# Adafruit_PiMiniTFT_240x240.net
KiCad netlist of a schematic drawn in EAGLE
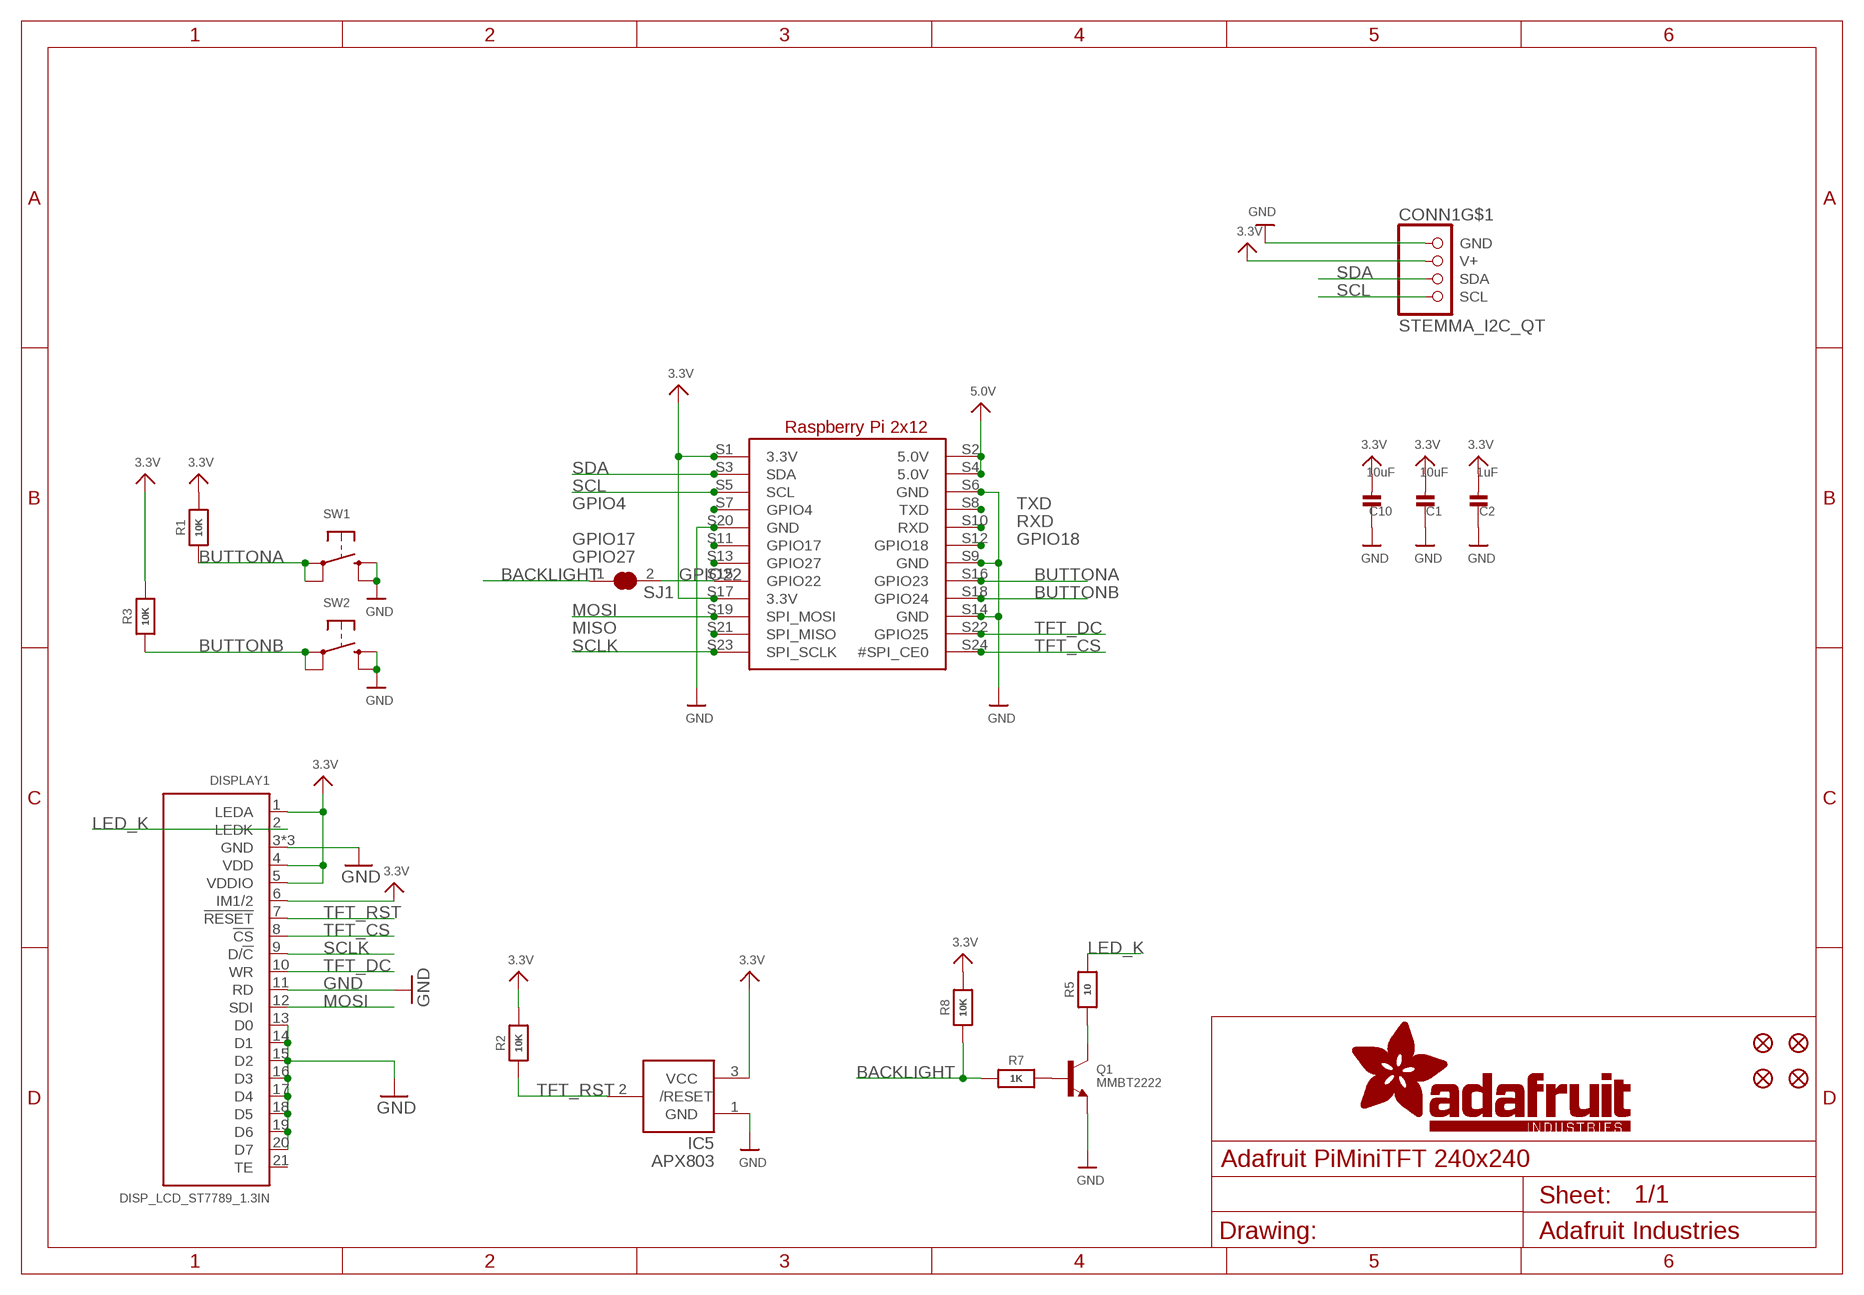
[diagram p0: schematic, sheet 1]

(export (version "E")
  (design (tool "Eeschema 10.0.6"))
  (components
    (comp (ref "C1")
      (value "10uF")
      (footprint "eagle-import:0805-NO")
      (libsource (lib "eagle-import") (part "CAP_CERAMIC0805-NOOUTLINE"))
    )
    (comp (ref "C2")
      (value "1uF")
      (footprint "eagle-import:0603-NO")
      (libsource (lib "eagle-import") (part "CAP_CERAMIC0603_NO"))
    )
    (comp (ref "C10")
      (value "10uF")
      (footprint "eagle-import:0805-NO")
      (libsource (lib "eagle-import") (part "CAP_CERAMIC0805-NOOUTLINE"))
    )
    (comp (ref "CONN1")
      (value "STEMMA_I2C_QT")
      (footprint "eagle-import:JST_SH4")
      (libsource (lib "eagle-import") (part "STEMMA_I2C_QT"))
    )
    (comp (ref "DISPLAY1")
      (value "DISP_LCD_ST7789_1.3IN")
      (footprint "eagle-import:TFT_1.3IN_240X240_24P")
      (libsource (lib "eagle-import") (part "DISP_LCD_ST7789_1.3IN"))
    )
    (comp (ref "FID1")
      (value "FIDUCIAL_1MM")
      (footprint "eagle-import:FIDUCIAL_1MM")
      (libsource (lib "eagle-import") (part "FIDUCIAL_1MM"))
    )
    (comp (ref "FID2")
      (value "FIDUCIAL_1MM")
      (footprint "eagle-import:FIDUCIAL_1MM")
      (libsource (lib "eagle-import") (part "FIDUCIAL_1MM"))
    )
    (comp (ref "FID3")
      (value "FIDUCIAL_1MM")
      (footprint "eagle-import:FIDUCIAL_1MM")
      (libsource (lib "eagle-import") (part "FIDUCIAL_1MM"))
    )
    (comp (ref "FID4")
      (value "FIDUCIAL_1MM")
      (footprint "eagle-import:FIDUCIAL_1MM")
      (libsource (lib "eagle-import") (part "FIDUCIAL_1MM"))
    )
    (comp (ref "IC5")
      (value "APX803")
      (footprint "eagle-import:SOT23")
      (libsource (lib "eagle-import") (part "AXP083-SAG"))
    )
    (comp (ref "Q1")
      (value "MMBT2222")
      (footprint "eagle-import:SOT23-WIDE")
      (libsource (lib "eagle-import") (part "TRANSISTOR_NPNWIDE"))
    )
    (comp (ref "R1")
      (value "10K")
      (footprint "eagle-import:0603-NO")
      (libsource (lib "eagle-import") (part "RESISTOR_0603_NOOUT"))
    )
    (comp (ref "R2")
      (value "10K")
      (footprint "eagle-import:0603-NO")
      (libsource (lib "eagle-import") (part "RESISTOR_0603_NOOUT"))
    )
    (comp (ref "R3")
      (value "10K")
      (footprint "eagle-import:0603-NO")
      (libsource (lib "eagle-import") (part "RESISTOR_0603_NOOUT"))
    )
    (comp (ref "R5")
      (value "10")
      (footprint "eagle-import:0603-NO")
      (libsource (lib "eagle-import") (part "RESISTOR_0603_NOOUT"))
    )
    (comp (ref "R7")
      (value "1K")
      (footprint "eagle-import:0603-NO")
      (libsource (lib "eagle-import") (part "RESISTOR_0603_NOOUT"))
    )
    (comp (ref "R8")
      (value "10K")
      (footprint "eagle-import:0603-NO")
      (libsource (lib "eagle-import") (part "RESISTOR_0603_NOOUT"))
    )
    (comp (ref "RASPI1")
      (value "RASPBERRYPI_2X12_SMT")
      (footprint "eagle-import:RASPBERRYPI_2X12_SMT")
      (libsource (lib "eagle-import") (part "RASPBERRYPI_2X12_SMT"))
    )
    (comp (ref "SJ1")
      (value "SOLDERJUMPER_CLOSED")
      (footprint "eagle-import:SOLDERJUMPER_CLOSEDWIRE")
      (libsource (lib "eagle-import") (part "SOLDERJUMPER_CLOSED"))
    )
    (comp (ref "SW1")
      (value "SWITCH_TACT_SMT_EVQQ2_SMALL")
      (footprint "eagle-import:EVQ-Q2_SMALLER")
      (libsource (lib "eagle-import") (part "SWITCH_TACT_SMT_EVQQ2_SMALL"))
    )
    (comp (ref "SW2")
      (value "SWITCH_TACT_SMT_EVQQ2_SMALL")
      (footprint "eagle-import:EVQ-Q2_SMALLER")
      (libsource (lib "eagle-import") (part "SWITCH_TACT_SMT_EVQQ2_SMALL"))
    )
  )
  (nets
    (net (code "1") (name "/BACKLIGHT") (class "Default")
      (node (ref "R7") (pin "1") (pinfunction "1_1") (pintype "passive"))
      (node (ref "R8") (pin "1") (pinfunction "1_1") (pintype "passive"))
      (node (ref "SJ1") (pin "1") (pinfunction "1_1") (pintype "passive"))
    )
    (net (code "2") (name "/BUTTONA") (class "Default")
      (node (ref "R1") (pin "1") (pinfunction "1_1") (pintype "passive"))
      (node (ref "RASPI1") (pin "S16") (pinfunction "GPIO23_S16") (pintype "bidirectional"))
      (node (ref "SW1") (pin "A") (pinfunction "P_A") (pintype "passive"))
      (node (ref "SW1") (pin "A'") (pinfunction "P1_A'") (pintype "passive"))
    )
    (net (code "3") (name "/BUTTONB") (class "Default")
      (node (ref "R3") (pin "1") (pinfunction "1_1") (pintype "passive"))
      (node (ref "RASPI1") (pin "S18") (pinfunction "GPIO24_S18") (pintype "bidirectional"))
      (node (ref "SW2") (pin "A") (pinfunction "P_A") (pintype "passive"))
      (node (ref "SW2") (pin "A'") (pinfunction "P1_A'") (pintype "passive"))
    )
    (net (code "4") (name "/GPIO4") (class "Default")
      (node (ref "RASPI1") (pin "S7") (pinfunction "GPIO4_S7") (pintype "bidirectional"))
    )
    (net (code "5") (name "/GPIO17") (class "Default")
      (node (ref "RASPI1") (pin "S11") (pinfunction "GPIO17_S11") (pintype "bidirectional"))
    )
    (net (code "6") (name "/GPIO18") (class "Default")
      (node (ref "RASPI1") (pin "S12") (pinfunction "GPIO18_S12") (pintype "bidirectional"))
    )
    (net (code "7") (name "/GPIO22") (class "Default")
      (node (ref "RASPI1") (pin "S15") (pinfunction "GPIO22_S15") (pintype "bidirectional"))
      (node (ref "SJ1") (pin "2") (pinfunction "2_2") (pintype "passive"))
    )
    (net (code "8") (name "/GPIO27") (class "Default")
      (node (ref "RASPI1") (pin "S13") (pinfunction "GPIO27_S13") (pintype "bidirectional"))
    )
    (net (code "9") (name "/LED_K") (class "Default")
      (node (ref "DISPLAY1") (pin "2") (pinfunction "LEDK_2") (pintype "input"))
      (node (ref "R5") (pin "2") (pinfunction "2_2") (pintype "passive"))
    )
    (net (code "10") (name "/MISO") (class "Default")
      (node (ref "RASPI1") (pin "S21") (pinfunction "SPI_MISO_S21") (pintype "bidirectional"))
    )
    (net (code "11") (name "/MOSI") (class "Default")
      (node (ref "DISPLAY1") (pin "12") (pinfunction "SDI_12") (pintype "input"))
      (node (ref "RASPI1") (pin "S19") (pinfunction "SPI_MOSI_S19") (pintype "bidirectional"))
    )
    (net (code "12") (name "/RXD") (class "Default")
      (node (ref "RASPI1") (pin "S10") (pinfunction "RXD_S10") (pintype "bidirectional"))
    )
    (net (code "13") (name "/SCL") (class "Default")
      (node (ref "CONN1") (pin "4") (pinfunction "SCL_4") (pintype "passive"))
      (node (ref "RASPI1") (pin "S5") (pinfunction "SCL_S5") (pintype "bidirectional"))
    )
    (net (code "14") (name "/SCLK") (class "Default")
      (node (ref "DISPLAY1") (pin "9") (pinfunction "D/~{C}_9") (pintype "input"))
      (node (ref "RASPI1") (pin "S23") (pinfunction "SPI_SCLK_S23") (pintype "bidirectional"))
    )
    (net (code "15") (name "/SDA") (class "Default")
      (node (ref "CONN1") (pin "3") (pinfunction "SDA_3") (pintype "passive"))
      (node (ref "RASPI1") (pin "S3") (pinfunction "SDA_S3") (pintype "bidirectional"))
    )
    (net (code "16") (name "/TFT_CS") (class "Default")
      (node (ref "DISPLAY1") (pin "8") (pinfunction "~{CS}_8") (pintype "input"))
      (node (ref "RASPI1") (pin "S24") (pinfunction "#SPI_CE0_S24") (pintype "bidirectional"))
    )
    (net (code "17") (name "/TFT_DC") (class "Default")
      (node (ref "DISPLAY1") (pin "10") (pinfunction "WR_10") (pintype "input"))
      (node (ref "RASPI1") (pin "S22") (pinfunction "GPIO25_S22") (pintype "bidirectional"))
    )
    (net (code "18") (name "/TFT_RST") (class "Default")
      (node (ref "DISPLAY1") (pin "7") (pinfunction "~{RESET}_7") (pintype "input"))
      (node (ref "IC5") (pin "2") (pinfunction "/RESET_2") (pintype "output"))
      (node (ref "R2") (pin "1") (pinfunction "1_1") (pintype "passive"))
    )
    (net (code "19") (name "/TXD") (class "Default")
      (node (ref "RASPI1") (pin "S8") (pinfunction "TXD_S8") (pintype "bidirectional"))
    )
    (net (code "20") (name "3.3V") (class "Default")
      (node (ref "C1") (pin "2") (pinfunction "2_2") (pintype "passive"))
      (node (ref "C10") (pin "2") (pinfunction "2_2") (pintype "passive"))
      (node (ref "C2") (pin "2") (pinfunction "2_2") (pintype "passive"))
      (node (ref "CONN1") (pin "2") (pinfunction "V+_2") (pintype "passive"))
      (node (ref "DISPLAY1") (pin "1") (pinfunction "LEDA_1") (pintype "input"))
      (node (ref "DISPLAY1") (pin "4") (pinfunction "VDD_4") (pintype "power_in"))
      (node (ref "DISPLAY1") (pin "5") (pinfunction "VDDIO_5") (pintype "power_in"))
      (node (ref "DISPLAY1") (pin "6") (pinfunction "IM1/2_6") (pintype "input"))
      (node (ref "IC5") (pin "3") (pinfunction "VCC_3") (pintype "power_in"))
      (node (ref "R1") (pin "2") (pinfunction "2_2") (pintype "passive"))
      (node (ref "R2") (pin "2") (pinfunction "2_2") (pintype "passive"))
      (node (ref "R3") (pin "2") (pinfunction "2_2") (pintype "passive"))
      (node (ref "R8") (pin "2") (pinfunction "2_2") (pintype "passive"))
      (node (ref "RASPI1") (pin "S1") (pinfunction "3.3V_S1") (pintype "power_in"))
      (node (ref "RASPI1") (pin "S17") (pinfunction "3.3V_S17") (pintype "power_in"))
    )
    (net (code "21") (name "5.0V") (class "Default")
      (node (ref "RASPI1") (pin "S2") (pinfunction "5.0V_S2") (pintype "power_in"))
      (node (ref "RASPI1") (pin "S4") (pinfunction "5.0V_S4") (pintype "power_in"))
    )
    (net (code "22") (name "GND") (class "Default")
      (node (ref "C1") (pin "1") (pinfunction "1_1") (pintype "passive"))
      (node (ref "C10") (pin "1") (pinfunction "1_1") (pintype "passive"))
      (node (ref "C2") (pin "1") (pinfunction "1_1") (pintype "passive"))
      (node (ref "CONN1") (pin "1") (pinfunction "GND_1") (pintype "passive"))
      (node (ref "DISPLAY1") (pin "11") (pinfunction "RD_11") (pintype "input"))
      (node (ref "DISPLAY1") (pin "13") (pinfunction "D0_13") (pintype "bidirectional"))
      (node (ref "DISPLAY1") (pin "14") (pinfunction "D1_14") (pintype "bidirectional"))
      (node (ref "DISPLAY1") (pin "15") (pinfunction "D2_15") (pintype "bidirectional"))
      (node (ref "DISPLAY1") (pin "16") (pinfunction "D3_16") (pintype "bidirectional"))
      (node (ref "DISPLAY1") (pin "17") (pinfunction "D4_17") (pintype "bidirectional"))
      (node (ref "DISPLAY1") (pin "18") (pinfunction "D5_18") (pintype "bidirectional"))
      (node (ref "DISPLAY1") (pin "19") (pinfunction "D6_19") (pintype "bidirectional"))
      (node (ref "DISPLAY1") (pin "20") (pinfunction "D7_20") (pintype "bidirectional"))
      (node (ref "DISPLAY1") (pin "23") (pinfunction "GND_23") (pintype "power_in"))
      (node (ref "DISPLAY1") (pin "24") (pinfunction "GND_24") (pintype "power_in"))
      (node (ref "DISPLAY1") (pin "3") (pinfunction "GND_3") (pintype "power_in"))
      (node (ref "IC5") (pin "1") (pinfunction "GND_1") (pintype "power_in"))
      (node (ref "Q1") (pin "2") (pinfunction "E_2") (pintype "passive"))
      (node (ref "RASPI1") (pin "S14") (pinfunction "GND_S14") (pintype "power_in"))
      (node (ref "RASPI1") (pin "S20") (pinfunction "GND_S20") (pintype "power_in"))
      (node (ref "RASPI1") (pin "S6") (pinfunction "GND_S6") (pintype "power_in"))
      (node (ref "RASPI1") (pin "S9") (pinfunction "GND_S9") (pintype "power_in"))
      (node (ref "SW1") (pin "B") (pinfunction "S_B") (pintype "passive"))
      (node (ref "SW1") (pin "B'") (pinfunction "S1_B'") (pintype "passive"))
      (node (ref "SW2") (pin "B") (pinfunction "S_B") (pintype "passive"))
      (node (ref "SW2") (pin "B'") (pinfunction "S1_B'") (pintype "passive"))
    )
    (net (code "23") (name "Net-(Q1-B)") (class "Default")
      (node (ref "Q1") (pin "1") (pinfunction "B_1") (pintype "passive"))
      (node (ref "R7") (pin "2") (pinfunction "2_2") (pintype "passive"))
    )
    (net (code "24") (name "Net-(Q1-C)") (class "Default")
      (node (ref "Q1") (pin "3") (pinfunction "C_3") (pintype "passive"))
      (node (ref "R5") (pin "1") (pinfunction "1_1") (pintype "passive"))
    )
    (net (code "25") (name "unconnected-(DISPLAY1-TE-Pad21)") (class "Default")
      (node (ref "DISPLAY1") (pin "21") (pinfunction "TE_21") (pintype "output"))
    )
  )
)
